# LichtschrankenArray.net
KiCad netlist of a schematic drawn in EAGLE
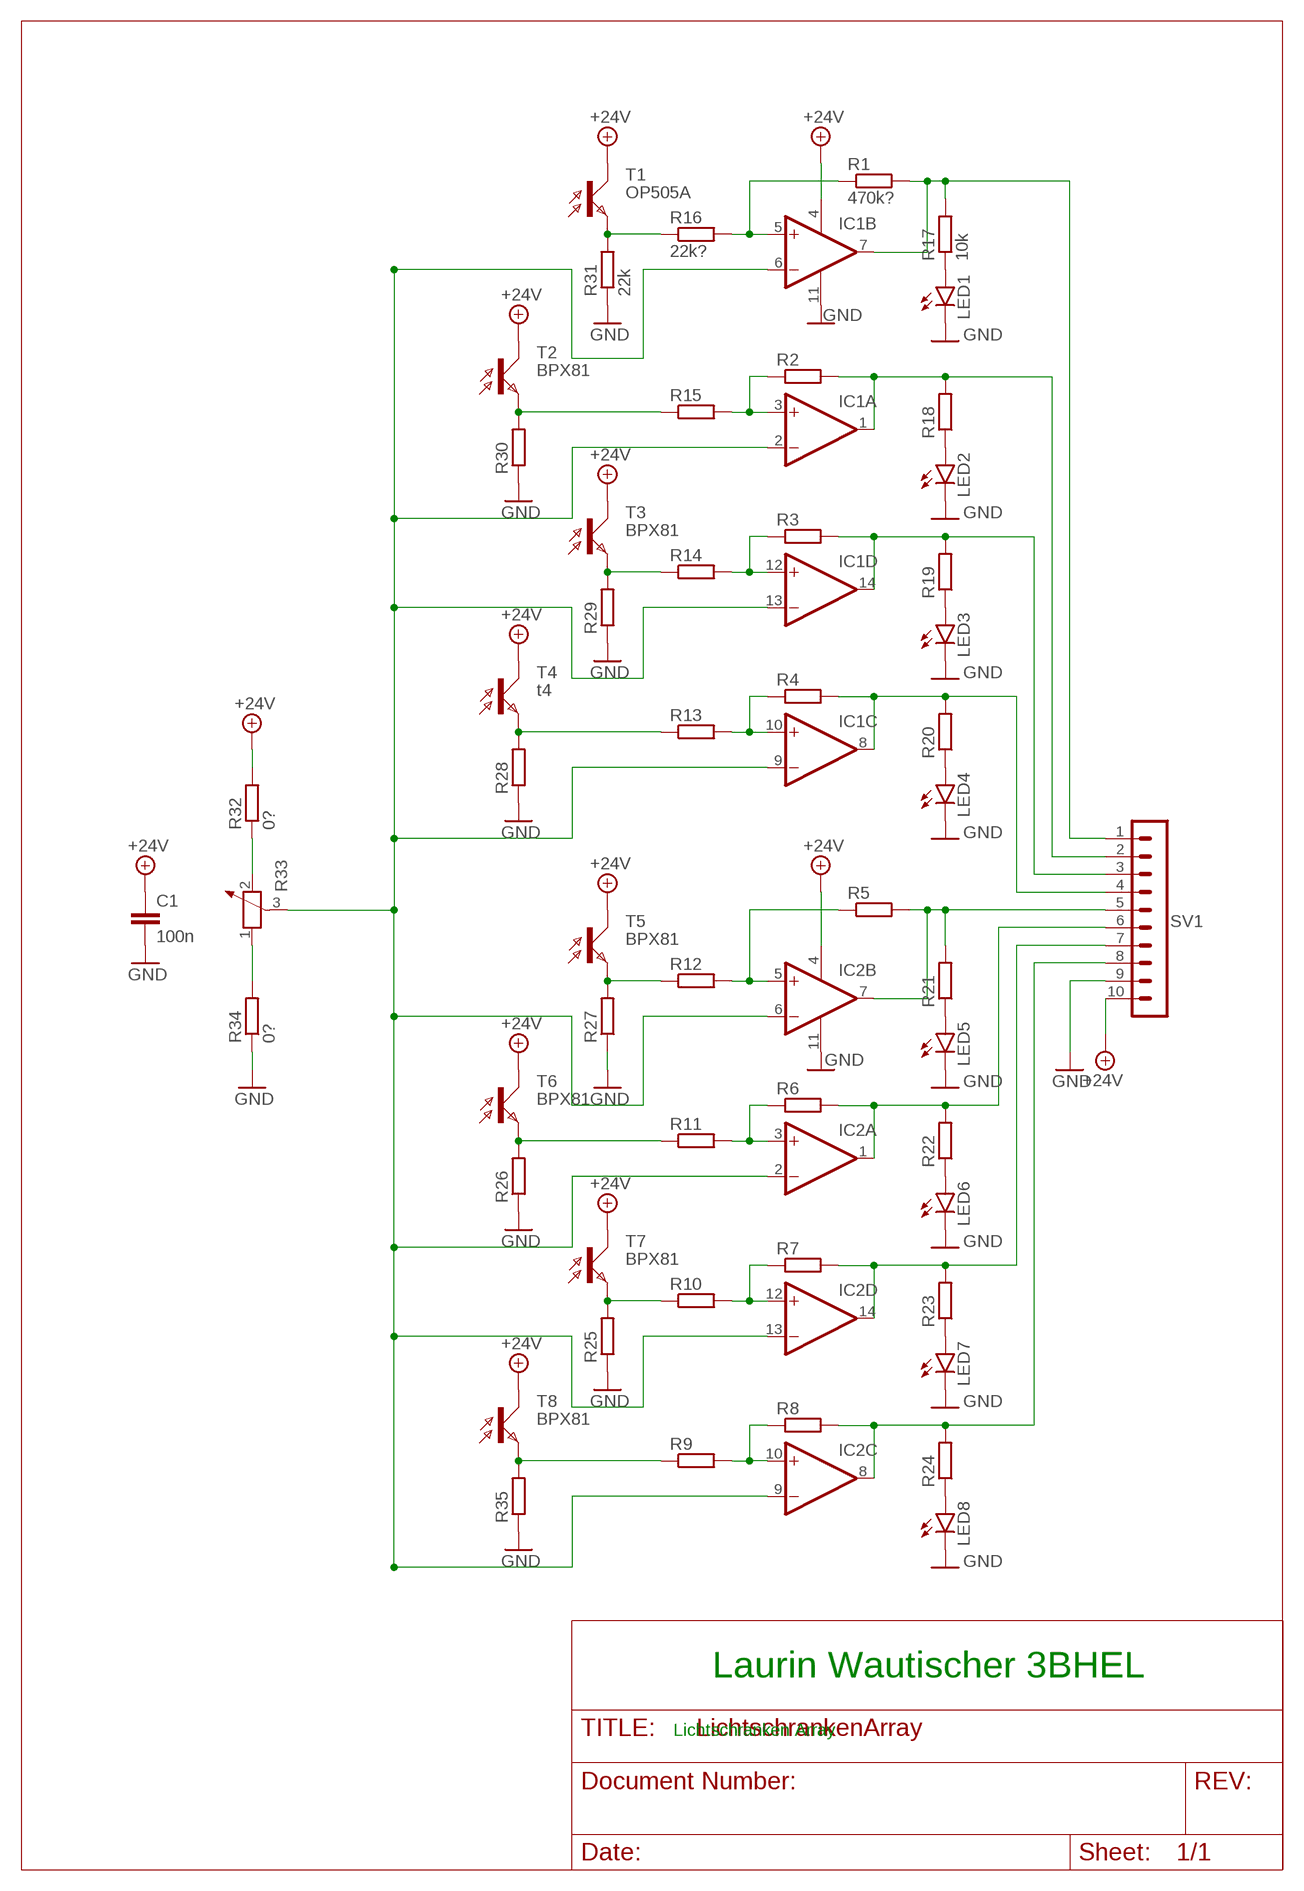
[diagram p0: schematic, sheet 1]

(export (version "E")
  (design (tool "Eeschema 10.0.6"))
  (components
    (comp (ref "C1")
      (value "100n")
      (footprint "eagle-import:C1206")
      (libsource (lib "eagle-import") (part "C-EUC1206"))
    )
    (comp (ref "IC1")
      (value "4AMP_P4+11N")
      (footprint "eagle-import:DIL14")
      (libsource (lib "eagle-import") (part "4AMP_P4+11N"))
    )
    (comp (ref "IC2")
      (value "4AMP_P4+11N")
      (footprint "eagle-import:DIL14")
      (libsource (lib "eagle-import") (part "4AMP_P4+11N"))
    )
    (comp (ref "LED1")
      (value "LEDSMT1206")
      (footprint "eagle-import:1206")
      (libsource (lib "eagle-import") (part "LEDSMT1206"))
    )
    (comp (ref "LED2")
      (value "LEDSMT1206")
      (footprint "eagle-import:1206")
      (libsource (lib "eagle-import") (part "LEDSMT1206"))
    )
    (comp (ref "LED3")
      (value "LEDSMT1206")
      (footprint "eagle-import:1206")
      (libsource (lib "eagle-import") (part "LEDSMT1206"))
    )
    (comp (ref "LED4")
      (value "LEDSMT1206")
      (footprint "eagle-import:1206")
      (libsource (lib "eagle-import") (part "LEDSMT1206"))
    )
    (comp (ref "LED5")
      (value "LEDSMT1206")
      (footprint "eagle-import:1206")
      (libsource (lib "eagle-import") (part "LEDSMT1206"))
    )
    (comp (ref "LED6")
      (value "LEDSMT1206")
      (footprint "eagle-import:1206")
      (libsource (lib "eagle-import") (part "LEDSMT1206"))
    )
    (comp (ref "LED7")
      (value "LEDSMT1206")
      (footprint "eagle-import:1206")
      (libsource (lib "eagle-import") (part "LEDSMT1206"))
    )
    (comp (ref "LED8")
      (value "LEDSMT1206")
      (footprint "eagle-import:1206")
      (libsource (lib "eagle-import") (part "LEDSMT1206"))
    )
    (comp (ref "R1")
      (value "470k?")
      (footprint "eagle-import:0207_10")
      (libsource (lib "eagle-import") (part "R-EU_0207/10"))
    )
    (comp (ref "R2")
      (value "R-EU_0207/10")
      (footprint "eagle-import:0207_10")
      (libsource (lib "eagle-import") (part "R-EU_0207/10"))
    )
    (comp (ref "R3")
      (value "R-EU_0207/10")
      (footprint "eagle-import:0207_10")
      (libsource (lib "eagle-import") (part "R-EU_0207/10"))
    )
    (comp (ref "R4")
      (value "R-EU_0207/10")
      (footprint "eagle-import:0207_10")
      (libsource (lib "eagle-import") (part "R-EU_0207/10"))
    )
    (comp (ref "R5")
      (value "R-EU_0207/10")
      (footprint "eagle-import:0207_10")
      (libsource (lib "eagle-import") (part "R-EU_0207/10"))
    )
    (comp (ref "R6")
      (value "R-EU_0207/10")
      (footprint "eagle-import:0207_10")
      (libsource (lib "eagle-import") (part "R-EU_0207/10"))
    )
    (comp (ref "R7")
      (value "R-EU_0207/10")
      (footprint "eagle-import:0207_10")
      (libsource (lib "eagle-import") (part "R-EU_0207/10"))
    )
    (comp (ref "R8")
      (value "R-EU_0207/10")
      (footprint "eagle-import:0207_10")
      (libsource (lib "eagle-import") (part "R-EU_0207/10"))
    )
    (comp (ref "R9")
      (value "R-EU_R1206")
      (footprint "eagle-import:R1206")
      (libsource (lib "eagle-import") (part "R-EU_R1206"))
    )
    (comp (ref "R10")
      (value "R-EU_R1206")
      (footprint "eagle-import:R1206")
      (libsource (lib "eagle-import") (part "R-EU_R1206"))
    )
    (comp (ref "R11")
      (value "R-EU_R1206")
      (footprint "eagle-import:R1206")
      (libsource (lib "eagle-import") (part "R-EU_R1206"))
    )
    (comp (ref "R12")
      (value "R-EU_R1206")
      (footprint "eagle-import:R1206")
      (libsource (lib "eagle-import") (part "R-EU_R1206"))
    )
    (comp (ref "R13")
      (value "R-EU_R1206")
      (footprint "eagle-import:R1206")
      (libsource (lib "eagle-import") (part "R-EU_R1206"))
    )
    (comp (ref "R14")
      (value "R-EU_R1206")
      (footprint "eagle-import:R1206")
      (libsource (lib "eagle-import") (part "R-EU_R1206"))
    )
    (comp (ref "R15")
      (value "R-EU_R1206")
      (footprint "eagle-import:R1206")
      (libsource (lib "eagle-import") (part "R-EU_R1206"))
    )
    (comp (ref "R16")
      (value "22k?")
      (footprint "eagle-import:R1206")
      (libsource (lib "eagle-import") (part "R-EU_R1206"))
    )
    (comp (ref "R17")
      (value "10k")
      (footprint "eagle-import:0207_10")
      (libsource (lib "eagle-import") (part "R-EU_0207/10"))
    )
    (comp (ref "R18")
      (value "R-EU_0207/10")
      (footprint "eagle-import:0207_10")
      (libsource (lib "eagle-import") (part "R-EU_0207/10"))
    )
    (comp (ref "R19")
      (value "R-EU_0207/10")
      (footprint "eagle-import:0207_10")
      (libsource (lib "eagle-import") (part "R-EU_0207/10"))
    )
    (comp (ref "R20")
      (value "R-EU_0207/10")
      (footprint "eagle-import:0207_10")
      (libsource (lib "eagle-import") (part "R-EU_0207/10"))
    )
    (comp (ref "R21")
      (value "R-EU_0207/10")
      (footprint "eagle-import:0207_10")
      (libsource (lib "eagle-import") (part "R-EU_0207/10"))
    )
    (comp (ref "R22")
      (value "R-EU_0207/10")
      (footprint "eagle-import:0207_10")
      (libsource (lib "eagle-import") (part "R-EU_0207/10"))
    )
    (comp (ref "R23")
      (value "R-EU_0207/10")
      (footprint "eagle-import:0207_10")
      (libsource (lib "eagle-import") (part "R-EU_0207/10"))
    )
    (comp (ref "R24")
      (value "R-EU_0207/10")
      (footprint "eagle-import:0207_10")
      (libsource (lib "eagle-import") (part "R-EU_0207/10"))
    )
    (comp (ref "R25")
      (value "R-EU_0207/10")
      (footprint "eagle-import:0207_10")
      (libsource (lib "eagle-import") (part "R-EU_0207/10"))
    )
    (comp (ref "R26")
      (value "R-EU_0207/10")
      (footprint "eagle-import:0207_10")
      (libsource (lib "eagle-import") (part "R-EU_0207/10"))
    )
    (comp (ref "R27")
      (value "R-EU_0207/10")
      (footprint "eagle-import:0207_10")
      (libsource (lib "eagle-import") (part "R-EU_0207/10"))
    )
    (comp (ref "R28")
      (value "R-EU_0207/10")
      (footprint "eagle-import:0207_10")
      (libsource (lib "eagle-import") (part "R-EU_0207/10"))
    )
    (comp (ref "R29")
      (value "R-EU_0207/10")
      (footprint "eagle-import:0207_10")
      (libsource (lib "eagle-import") (part "R-EU_0207/10"))
    )
    (comp (ref "R30")
      (value "R-EU_0207/10")
      (footprint "eagle-import:0207_10")
      (libsource (lib "eagle-import") (part "R-EU_0207/10"))
    )
    (comp (ref "R31")
      (value "22k")
      (footprint "eagle-import:0207_10")
      (libsource (lib "eagle-import") (part "R-EU_0207/10"))
    )
    (comp (ref "R32")
      (value "0?")
      (footprint "eagle-import:0207_10")
      (libsource (lib "eagle-import") (part "R-EU_0207/10"))
    )
    (comp (ref "R33")
      (value "POTENTIOMETER_PT-10")
      (footprint "eagle-import:PT-10")
      (libsource (lib "eagle-import") (part "POTENTIOMETER_PT-10"))
    )
    (comp (ref "R34")
      (value "0?")
      (footprint "eagle-import:0207_10")
      (libsource (lib "eagle-import") (part "R-EU_0207/10"))
    )
    (comp (ref "R35")
      (value "R-EU_0207/10")
      (footprint "eagle-import:0207_10")
      (libsource (lib "eagle-import") (part "R-EU_0207/10"))
    )
    (comp (ref "SV1")
      (value "MA10-1")
      (footprint "eagle-import:MA10-1")
      (libsource (lib "eagle-import") (part "MA10-1"))
    )
    (comp (ref "T1")
      (value "OP505A")
      (footprint "eagle-import:BPX81")
      (libsource (lib "eagle-import") (part "BPX81"))
    )
    (comp (ref "T2")
      (value "BPX81")
      (footprint "eagle-import:BPX81")
      (libsource (lib "eagle-import") (part "BPX81"))
    )
    (comp (ref "T3")
      (value "BPX81")
      (footprint "eagle-import:BPX81")
      (libsource (lib "eagle-import") (part "BPX81"))
    )
    (comp (ref "T4")
      (value "t4")
      (footprint "eagle-import:BPX81")
      (libsource (lib "eagle-import") (part "BPX81"))
    )
    (comp (ref "T5")
      (value "BPX81")
      (footprint "eagle-import:BPX81")
      (libsource (lib "eagle-import") (part "BPX81"))
    )
    (comp (ref "T6")
      (value "BPX81")
      (footprint "eagle-import:BPX81")
      (libsource (lib "eagle-import") (part "BPX81"))
    )
    (comp (ref "T7")
      (value "BPX81")
      (footprint "eagle-import:BPX81")
      (libsource (lib "eagle-import") (part "BPX81"))
    )
    (comp (ref "T8")
      (value "BPX81")
      (footprint "eagle-import:BPX81")
      (libsource (lib "eagle-import") (part "BPX81"))
    )
  )
  (nets
    (net (code "1") (name "+24V") (class "Default")
      (node (ref "C1") (pin "1") (pinfunction "1_1") (pintype "passive"))
      (node (ref "IC1") (pin "4") (pinfunction "V+_4") (pintype "power_in"))
      (node (ref "IC2") (pin "4") (pinfunction "V+_4") (pintype "power_in"))
      (node (ref "R32") (pin "2") (pinfunction "2_2") (pintype "passive"))
      (node (ref "SV1") (pin "10") (pinfunction "10_10") (pintype "passive"))
      (node (ref "T1") (pin "C") (pinfunction "C_C") (pintype "passive"))
      (node (ref "T2") (pin "C") (pinfunction "C_C") (pintype "passive"))
      (node (ref "T3") (pin "C") (pinfunction "C_C") (pintype "passive"))
      (node (ref "T4") (pin "C") (pinfunction "C_C") (pintype "passive"))
      (node (ref "T5") (pin "C") (pinfunction "C_C") (pintype "passive"))
      (node (ref "T6") (pin "C") (pinfunction "C_C") (pintype "passive"))
      (node (ref "T7") (pin "C") (pinfunction "C_C") (pintype "passive"))
      (node (ref "T8") (pin "C") (pinfunction "C_C") (pintype "passive"))
    )
    (net (code "2") (name "GND") (class "Default")
      (node (ref "C1") (pin "2") (pinfunction "2_2") (pintype "passive"))
      (node (ref "IC1") (pin "11") (pinfunction "V-_11") (pintype "power_in"))
      (node (ref "IC2") (pin "11") (pinfunction "V-_11") (pintype "power_in"))
      (node (ref "LED1") (pin "C") (pinfunction "C_C") (pintype "passive"))
      (node (ref "LED2") (pin "C") (pinfunction "C_C") (pintype "passive"))
      (node (ref "LED3") (pin "C") (pinfunction "C_C") (pintype "passive"))
      (node (ref "LED4") (pin "C") (pinfunction "C_C") (pintype "passive"))
      (node (ref "LED5") (pin "C") (pinfunction "C_C") (pintype "passive"))
      (node (ref "LED6") (pin "C") (pinfunction "C_C") (pintype "passive"))
      (node (ref "LED7") (pin "C") (pinfunction "C_C") (pintype "passive"))
      (node (ref "LED8") (pin "C") (pinfunction "C_C") (pintype "passive"))
      (node (ref "R25") (pin "1") (pinfunction "1_1") (pintype "passive"))
      (node (ref "R26") (pin "1") (pinfunction "1_1") (pintype "passive"))
      (node (ref "R27") (pin "1") (pinfunction "1_1") (pintype "passive"))
      (node (ref "R28") (pin "1") (pinfunction "1_1") (pintype "passive"))
      (node (ref "R29") (pin "1") (pinfunction "1_1") (pintype "passive"))
      (node (ref "R30") (pin "1") (pinfunction "1_1") (pintype "passive"))
      (node (ref "R31") (pin "1") (pinfunction "1_1") (pintype "passive"))
      (node (ref "R34") (pin "1") (pinfunction "1_1") (pintype "passive"))
      (node (ref "R35") (pin "1") (pinfunction "1_1") (pintype "passive"))
      (node (ref "SV1") (pin "9") (pinfunction "9_9") (pintype "passive"))
    )
    (net (code "3") (name "Net-(IC1A-+IN)") (class "Default")
      (node (ref "IC1") (pin "3") (pinfunction "+IN_3") (pintype "input"))
      (node (ref "R15") (pin "2") (pinfunction "2_2") (pintype "passive"))
      (node (ref "R2") (pin "1") (pinfunction "1_1") (pintype "passive"))
    )
    (net (code "4") (name "Net-(IC1A--IN)") (class "Default")
      (node (ref "IC1") (pin "13") (pinfunction "-IN_13") (pintype "input"))
      (node (ref "IC1") (pin "2") (pinfunction "-IN_2") (pintype "input"))
      (node (ref "IC1") (pin "6") (pinfunction "-IN_6") (pintype "input"))
      (node (ref "IC1") (pin "9") (pinfunction "-IN_9") (pintype "input"))
      (node (ref "IC2") (pin "13") (pinfunction "-IN_13") (pintype "input"))
      (node (ref "IC2") (pin "2") (pinfunction "-IN_2") (pintype "input"))
      (node (ref "IC2") (pin "6") (pinfunction "-IN_6") (pintype "input"))
      (node (ref "IC2") (pin "9") (pinfunction "-IN_9") (pintype "input"))
      (node (ref "R33") (pin "3") (pinfunction "3_3") (pintype "passive"))
    )
    (net (code "5") (name "Net-(IC1A-OUT)") (class "Default")
      (node (ref "IC1") (pin "1") (pinfunction "OUT_1") (pintype "output"))
      (node (ref "R18") (pin "2") (pinfunction "2_2") (pintype "passive"))
      (node (ref "R2") (pin "2") (pinfunction "2_2") (pintype "passive"))
      (node (ref "SV1") (pin "2") (pinfunction "2_2") (pintype "passive"))
    )
    (net (code "6") (name "Net-(IC1B-+IN)") (class "Default")
      (node (ref "IC1") (pin "5") (pinfunction "+IN_5") (pintype "input"))
      (node (ref "R1") (pin "1") (pinfunction "1_1") (pintype "passive"))
      (node (ref "R16") (pin "2") (pinfunction "2_2") (pintype "passive"))
    )
    (net (code "7") (name "Net-(IC1B-OUT)") (class "Default")
      (node (ref "IC1") (pin "7") (pinfunction "OUT_7") (pintype "output"))
      (node (ref "R1") (pin "2") (pinfunction "2_2") (pintype "passive"))
      (node (ref "R17") (pin "2") (pinfunction "2_2") (pintype "passive"))
      (node (ref "SV1") (pin "1") (pinfunction "1_1") (pintype "passive"))
    )
    (net (code "8") (name "Net-(IC1C-+IN)") (class "Default")
      (node (ref "IC1") (pin "10") (pinfunction "+IN_10") (pintype "input"))
      (node (ref "R13") (pin "2") (pinfunction "2_2") (pintype "passive"))
      (node (ref "R4") (pin "1") (pinfunction "1_1") (pintype "passive"))
    )
    (net (code "9") (name "Net-(IC1C-OUT)") (class "Default")
      (node (ref "IC1") (pin "8") (pinfunction "OUT_8") (pintype "output"))
      (node (ref "R20") (pin "2") (pinfunction "2_2") (pintype "passive"))
      (node (ref "R4") (pin "2") (pinfunction "2_2") (pintype "passive"))
      (node (ref "SV1") (pin "4") (pinfunction "4_4") (pintype "passive"))
    )
    (net (code "10") (name "Net-(IC1D-+IN)") (class "Default")
      (node (ref "IC1") (pin "12") (pinfunction "+IN_12") (pintype "input"))
      (node (ref "R14") (pin "2") (pinfunction "2_2") (pintype "passive"))
      (node (ref "R3") (pin "1") (pinfunction "1_1") (pintype "passive"))
    )
    (net (code "11") (name "Net-(IC1D-OUT)") (class "Default")
      (node (ref "IC1") (pin "14") (pinfunction "OUT_14") (pintype "output"))
      (node (ref "R19") (pin "2") (pinfunction "2_2") (pintype "passive"))
      (node (ref "R3") (pin "2") (pinfunction "2_2") (pintype "passive"))
      (node (ref "SV1") (pin "3") (pinfunction "3_3") (pintype "passive"))
    )
    (net (code "12") (name "Net-(IC2A-+IN)") (class "Default")
      (node (ref "IC2") (pin "3") (pinfunction "+IN_3") (pintype "input"))
      (node (ref "R11") (pin "2") (pinfunction "2_2") (pintype "passive"))
      (node (ref "R6") (pin "1") (pinfunction "1_1") (pintype "passive"))
    )
    (net (code "13") (name "Net-(IC2A-OUT)") (class "Default")
      (node (ref "IC2") (pin "1") (pinfunction "OUT_1") (pintype "output"))
      (node (ref "R22") (pin "2") (pinfunction "2_2") (pintype "passive"))
      (node (ref "R6") (pin "2") (pinfunction "2_2") (pintype "passive"))
      (node (ref "SV1") (pin "6") (pinfunction "6_6") (pintype "passive"))
    )
    (net (code "14") (name "Net-(IC2B-+IN)") (class "Default")
      (node (ref "IC2") (pin "5") (pinfunction "+IN_5") (pintype "input"))
      (node (ref "R12") (pin "2") (pinfunction "2_2") (pintype "passive"))
      (node (ref "R5") (pin "1") (pinfunction "1_1") (pintype "passive"))
    )
    (net (code "15") (name "Net-(IC2B-OUT)") (class "Default")
      (node (ref "IC2") (pin "7") (pinfunction "OUT_7") (pintype "output"))
      (node (ref "R21") (pin "2") (pinfunction "2_2") (pintype "passive"))
      (node (ref "R5") (pin "2") (pinfunction "2_2") (pintype "passive"))
      (node (ref "SV1") (pin "5") (pinfunction "5_5") (pintype "passive"))
    )
    (net (code "16") (name "Net-(IC2C-+IN)") (class "Default")
      (node (ref "IC2") (pin "10") (pinfunction "+IN_10") (pintype "input"))
      (node (ref "R8") (pin "1") (pinfunction "1_1") (pintype "passive"))
      (node (ref "R9") (pin "2") (pinfunction "2_2") (pintype "passive"))
    )
    (net (code "17") (name "Net-(IC2C-OUT)") (class "Default")
      (node (ref "IC2") (pin "8") (pinfunction "OUT_8") (pintype "output"))
      (node (ref "R24") (pin "2") (pinfunction "2_2") (pintype "passive"))
      (node (ref "R8") (pin "2") (pinfunction "2_2") (pintype "passive"))
      (node (ref "SV1") (pin "8") (pinfunction "8_8") (pintype "passive"))
    )
    (net (code "18") (name "Net-(IC2D-+IN)") (class "Default")
      (node (ref "IC2") (pin "12") (pinfunction "+IN_12") (pintype "input"))
      (node (ref "R10") (pin "2") (pinfunction "2_2") (pintype "passive"))
      (node (ref "R7") (pin "1") (pinfunction "1_1") (pintype "passive"))
    )
    (net (code "19") (name "Net-(IC2D-OUT)") (class "Default")
      (node (ref "IC2") (pin "14") (pinfunction "OUT_14") (pintype "output"))
      (node (ref "R23") (pin "2") (pinfunction "2_2") (pintype "passive"))
      (node (ref "R7") (pin "2") (pinfunction "2_2") (pintype "passive"))
      (node (ref "SV1") (pin "7") (pinfunction "7_7") (pintype "passive"))
    )
    (net (code "20") (name "Net-(LED1-PadA)") (class "Default")
      (node (ref "LED1") (pin "A") (pinfunction "A_A") (pintype "passive"))
      (node (ref "R17") (pin "1") (pinfunction "1_1") (pintype "passive"))
    )
    (net (code "21") (name "Net-(LED2-PadA)") (class "Default")
      (node (ref "LED2") (pin "A") (pinfunction "A_A") (pintype "passive"))
      (node (ref "R18") (pin "1") (pinfunction "1_1") (pintype "passive"))
    )
    (net (code "22") (name "Net-(LED3-PadA)") (class "Default")
      (node (ref "LED3") (pin "A") (pinfunction "A_A") (pintype "passive"))
      (node (ref "R19") (pin "1") (pinfunction "1_1") (pintype "passive"))
    )
    (net (code "23") (name "Net-(LED4-PadA)") (class "Default")
      (node (ref "LED4") (pin "A") (pinfunction "A_A") (pintype "passive"))
      (node (ref "R20") (pin "1") (pinfunction "1_1") (pintype "passive"))
    )
    (net (code "24") (name "Net-(LED5-PadA)") (class "Default")
      (node (ref "LED5") (pin "A") (pinfunction "A_A") (pintype "passive"))
      (node (ref "R21") (pin "1") (pinfunction "1_1") (pintype "passive"))
    )
    (net (code "25") (name "Net-(LED6-PadA)") (class "Default")
      (node (ref "LED6") (pin "A") (pinfunction "A_A") (pintype "passive"))
      (node (ref "R22") (pin "1") (pinfunction "1_1") (pintype "passive"))
    )
    (net (code "26") (name "Net-(LED7-PadA)") (class "Default")
      (node (ref "LED7") (pin "A") (pinfunction "A_A") (pintype "passive"))
      (node (ref "R23") (pin "1") (pinfunction "1_1") (pintype "passive"))
    )
    (net (code "27") (name "Net-(LED8-PadA)") (class "Default")
      (node (ref "LED8") (pin "A") (pinfunction "A_A") (pintype "passive"))
      (node (ref "R24") (pin "1") (pinfunction "1_1") (pintype "passive"))
    )
    (net (code "28") (name "Net-(R10-Pad1)") (class "Default")
      (node (ref "R10") (pin "1") (pinfunction "1_1") (pintype "passive"))
      (node (ref "R25") (pin "2") (pinfunction "2_2") (pintype "passive"))
      (node (ref "T7") (pin "E") (pinfunction "E_E") (pintype "passive"))
    )
    (net (code "29") (name "Net-(R11-Pad1)") (class "Default")
      (node (ref "R11") (pin "1") (pinfunction "1_1") (pintype "passive"))
      (node (ref "R26") (pin "2") (pinfunction "2_2") (pintype "passive"))
      (node (ref "T6") (pin "E") (pinfunction "E_E") (pintype "passive"))
    )
    (net (code "30") (name "Net-(R12-Pad1)") (class "Default")
      (node (ref "R12") (pin "1") (pinfunction "1_1") (pintype "passive"))
      (node (ref "R27") (pin "2") (pinfunction "2_2") (pintype "passive"))
      (node (ref "T5") (pin "E") (pinfunction "E_E") (pintype "passive"))
    )
    (net (code "31") (name "Net-(R13-Pad1)") (class "Default")
      (node (ref "R13") (pin "1") (pinfunction "1_1") (pintype "passive"))
      (node (ref "R28") (pin "2") (pinfunction "2_2") (pintype "passive"))
      (node (ref "T4") (pin "E") (pinfunction "E_E") (pintype "passive"))
    )
    (net (code "32") (name "Net-(R14-Pad1)") (class "Default")
      (node (ref "R14") (pin "1") (pinfunction "1_1") (pintype "passive"))
      (node (ref "R29") (pin "2") (pinfunction "2_2") (pintype "passive"))
      (node (ref "T3") (pin "E") (pinfunction "E_E") (pintype "passive"))
    )
    (net (code "33") (name "Net-(R15-Pad1)") (class "Default")
      (node (ref "R15") (pin "1") (pinfunction "1_1") (pintype "passive"))
      (node (ref "R30") (pin "2") (pinfunction "2_2") (pintype "passive"))
      (node (ref "T2") (pin "E") (pinfunction "E_E") (pintype "passive"))
    )
    (net (code "34") (name "Net-(R16-Pad1)") (class "Default")
      (node (ref "R16") (pin "1") (pinfunction "1_1") (pintype "passive"))
      (node (ref "R31") (pin "2") (pinfunction "2_2") (pintype "passive"))
      (node (ref "T1") (pin "E") (pinfunction "E_E") (pintype "passive"))
    )
    (net (code "35") (name "Net-(R32-Pad1)") (class "Default")
      (node (ref "R32") (pin "1") (pinfunction "1_1") (pintype "passive"))
      (node (ref "R33") (pin "2") (pinfunction "2_2") (pintype "passive"))
    )
    (net (code "36") (name "Net-(R33-Pad1)") (class "Default")
      (node (ref "R33") (pin "1") (pinfunction "1_1") (pintype "passive"))
      (node (ref "R34") (pin "2") (pinfunction "2_2") (pintype "passive"))
    )
    (net (code "37") (name "Net-(R35-Pad2)") (class "Default")
      (node (ref "R35") (pin "2") (pinfunction "2_2") (pintype "passive"))
      (node (ref "R9") (pin "1") (pinfunction "1_1") (pintype "passive"))
      (node (ref "T8") (pin "E") (pinfunction "E_E") (pintype "passive"))
    )
  )
)
